# mainsheet.net
KiCad netlist of a schematic drawn in Altium Designer
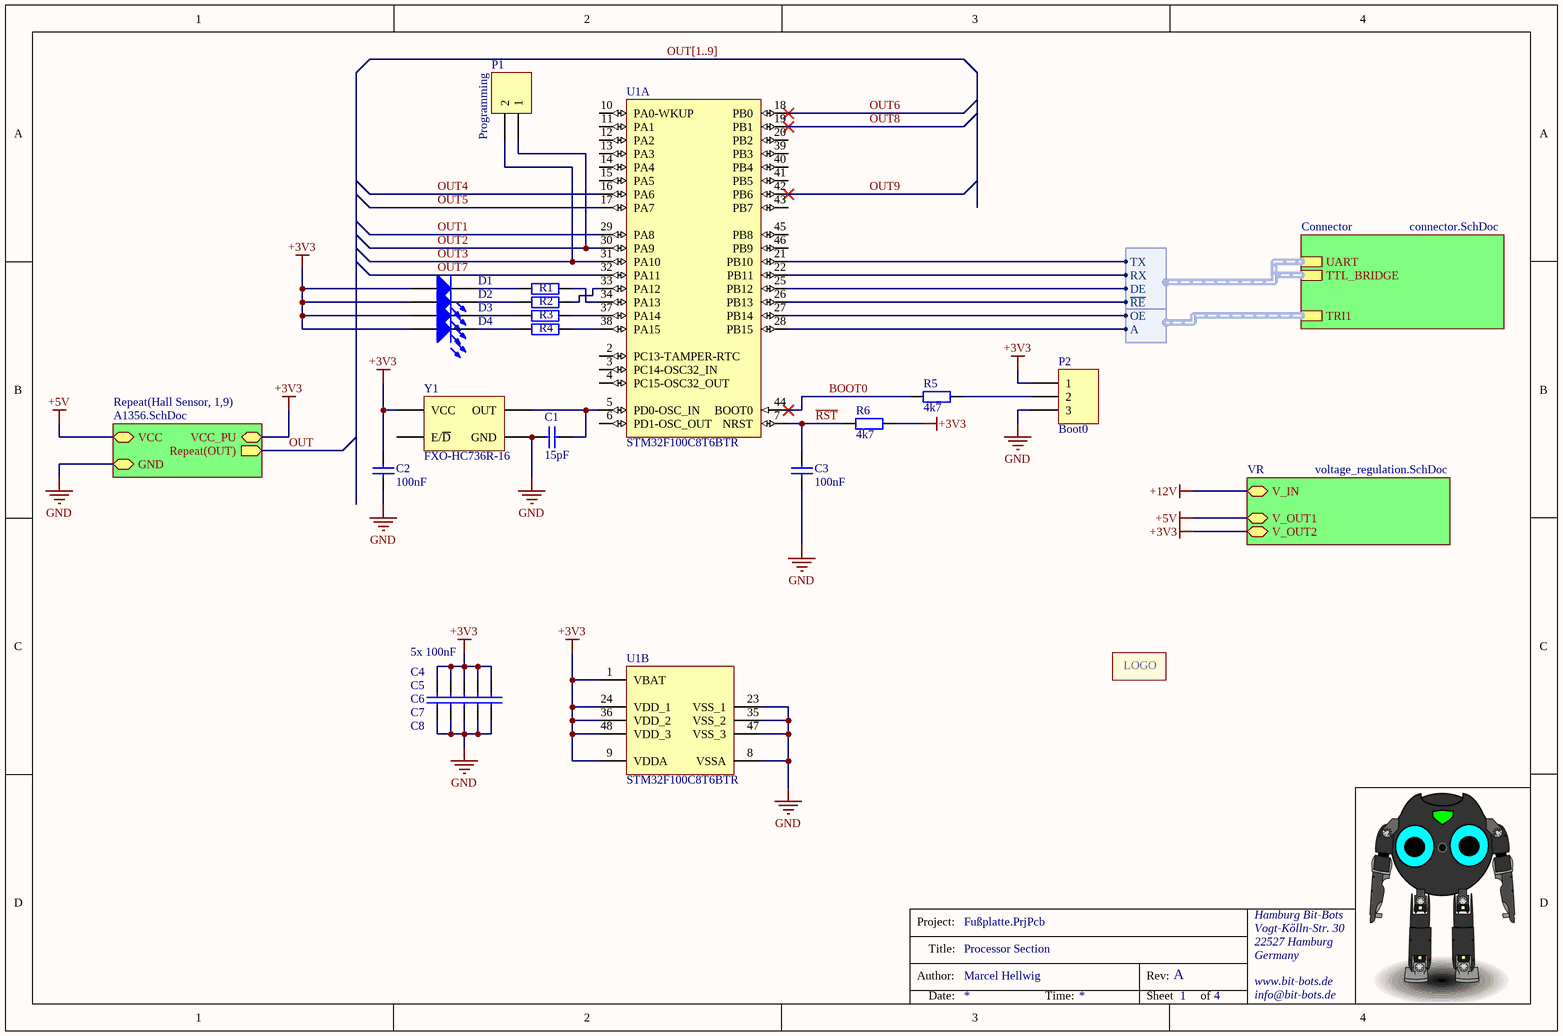
[diagram p0: mainsheet.SchDoc]

(export (version "E")
  (design (tool "Eeschema 10.0.6"))
  (components
    (comp (ref "C1")
      (value "15pF")
      (footprint "C2012")
      (description "Capacitor")
      (fields
        (field (name "MANUFACTURER") "MULTICOMP")
        (field (name "MANUFACTURER PART NUMBER") "MC0805N150J500CT")
        (field (name "PUBLISHER") "Altium Limited")
      )
      (libsource (lib "Miscellaneous Devices") (part "Cap"))
    )
    (comp (ref "C2")
      (value "100nF")
      (footprint "C2012")
      (description "Capacitor")
      (fields (field (name "PUBLISHER") "Altium Limited"))
      (libsource (lib "Miscellaneous Devices") (part "Cap"))
    )
    (comp (ref "C3")
      (value "100nF")
      (footprint "C2012")
      (description "Capacitor")
      (fields (field (name "PUBLISHER") "Altium Limited"))
      (libsource (lib "Miscellaneous Devices") (part "Cap"))
    )
    (comp (ref "C4")
      (value "100nF")
      (footprint "C2012")
      (description "Capacitor")
      (fields (field (name "PUBLISHER") "Altium Limited"))
      (libsource (lib "Miscellaneous Devices") (part "Cap"))
    )
    (comp (ref "C5")
      (value "100nF")
      (footprint "C2012")
      (description "Capacitor")
      (fields (field (name "PUBLISHER") "Altium Limited"))
      (libsource (lib "Miscellaneous Devices") (part "Cap"))
    )
    (comp (ref "C6")
      (value "100nF")
      (footprint "C2012")
      (description "Capacitor")
      (fields (field (name "PUBLISHER") "Altium Limited"))
      (libsource (lib "Miscellaneous Devices") (part "Cap"))
    )
    (comp (ref "C7")
      (value "100nF")
      (footprint "C2012")
      (description "Capacitor")
      (fields (field (name "PUBLISHER") "Altium Limited"))
      (libsource (lib "Miscellaneous Devices") (part "Cap"))
    )
    (comp (ref "C8")
      (value "100nF")
      (footprint "C2012")
      (description "Capacitor")
      (fields (field (name "PUBLISHER") "Altium Limited"))
      (libsource (lib "Miscellaneous Devices") (part "Cap"))
    )
    (comp (ref "D1")
      (value "Green")
      (footprint "MLCC2")
      (description "Typical INFRARED GaAs LED")
      (fields
        (field (name "MANUFACTURER") "VISHAY")
        (field (name "MANUFACTURER PART NUMBER") "VLMC3100-GS08")
        (field (name "PUBLISHER") "Altium Limited")
      )
      (libsource (lib "Miscellaneous Devices") (part "LED0"))
    )
    (comp (ref "D2")
      (value "Green")
      (footprint "MLCC2")
      (description "Typical INFRARED GaAs LED")
      (fields
        (field (name "MANUFACTURER") "VISHAY")
        (field (name "MANUFACTURER PART NUMBER") "VLMC3100-GS08")
        (field (name "PUBLISHER") "Altium Limited")
      )
      (libsource (lib "Miscellaneous Devices") (part "LED0"))
    )
    (comp (ref "D3")
      (value "Green")
      (footprint "MLCC2")
      (description "Typical INFRARED GaAs LED")
      (fields
        (field (name "MANUFACTURER") "VISHAY")
        (field (name "MANUFACTURER PART NUMBER") "VLMC3100-GS08")
        (field (name "PUBLISHER") "Altium Limited")
      )
      (libsource (lib "Miscellaneous Devices") (part "LED0"))
    )
    (comp (ref "D4")
      (value "Green")
      (footprint "MLCC2")
      (description "Typical INFRARED GaAs LED")
      (fields
        (field (name "MANUFACTURER") "VISHAY")
        (field (name "MANUFACTURER PART NUMBER") "VLMC3100-GS08")
        (field (name "PUBLISHER") "Altium Limited")
      )
      (libsource (lib "Miscellaneous Devices") (part "LED0"))
    )
    (comp (ref "Logo1")
      (value "Hamburg Bit-Bots Logo")
      (footprint "Logo")
      (libsource (lib "bitbots") (part "Logo"))
    )
    (comp (ref "P1")
      (value "Programming")
      (footprint "HDR1X2")
      (description "Header, 2-Pin")
      (fields (field (name "PUBLISHER") "Altium Limited"))
      (libsource (lib "Miscellaneous Connectors") (part "Header 2"))
    )
    (comp (ref "P2")
      (value "Boot0")
      (footprint "HDR1X3")
      (description "Header, 3-Pin")
      (fields (field (name "PUBLISHER") "Altium Limited"))
      (libsource (lib "Miscellaneous Connectors") (part "Header 3"))
    )
    (comp (ref "R1")
      (value "1k")
      (footprint "R2012")
      (description "Resistor")
      (fields
        (field (name "MANUFACTURER") "MULTICOMP")
        (field (name "MANUFACTURER PART NUMBER") "MC01W0805110K")
        (field (name "PUBLISHER") "Altium Limited")
      )
      (libsource (lib "Miscellaneous Devices") (part "Res2"))
    )
    (comp (ref "R2")
      (value "1k")
      (footprint "R2012")
      (description "Resistor")
      (fields
        (field (name "MANUFACTURER") "MULTICOMP")
        (field (name "MANUFACTURER PART NUMBER") "MC01W0805110K")
        (field (name "PUBLISHER") "Altium Limited")
      )
      (libsource (lib "Miscellaneous Devices") (part "Res2"))
    )
    (comp (ref "R3")
      (value "1k")
      (footprint "R2012")
      (description "Resistor")
      (fields
        (field (name "MANUFACTURER") "MULTICOMP")
        (field (name "MANUFACTURER PART NUMBER") "MC01W0805110K")
        (field (name "PUBLISHER") "Altium Limited")
      )
      (libsource (lib "Miscellaneous Devices") (part "Res2"))
    )
    (comp (ref "R4")
      (value "1k")
      (footprint "R2012")
      (description "Resistor")
      (fields
        (field (name "MANUFACTURER") "MULTICOMP")
        (field (name "MANUFACTURER PART NUMBER") "MC01W0805110K")
        (field (name "PUBLISHER") "Altium Limited")
      )
      (libsource (lib "Miscellaneous Devices") (part "Res2"))
    )
    (comp (ref "R5")
      (value "4k7")
      (footprint "R2012")
      (description "Resistor")
      (fields (field (name "PUBLISHER") "Altium Limited"))
      (libsource (lib "") (part "Res2_1"))
    )
    (comp (ref "R6")
      (value "4k7")
      (footprint "R2012")
      (description "Resistor")
      (fields (field (name "PUBLISHER") "Altium Limited"))
      (libsource (lib "") (part "Res2_1"))
    )
    (comp (ref "U1")
      (value "STM32F100C8T6BTR")
      (footprint "STM-LQFP48_L")
      (libsource (lib "Altium Content Vault") (part "MC-ARM-STM32F100X4_6_8_B-SQ48"))
    )
    (comp (ref "Y1")
      (value "FXO-HC736R-16")
      (footprint "FXO-HC73")
      (description "Oscillator with Enable Input")
      (libsource (lib "bitbots") (part "Oszillator"))
    )
  )
  (nets
    (net (code "3") (name "+3V3") (class "Default")
      (node (ref "C2") (pin "1") (pinfunction "1_1") (pintype "passive"))
      (node (ref "C4") (pin "2") (pinfunction "2_2") (pintype "passive"))
      (node (ref "C5") (pin "2") (pinfunction "2_2") (pintype "passive"))
      (node (ref "C6") (pin "2") (pinfunction "2_2") (pintype "passive"))
      (node (ref "C7") (pin "2") (pinfunction "2_2") (pintype "passive"))
      (node (ref "C8") (pin "2") (pinfunction "2_2") (pintype "passive"))
      (node (ref "D1") (pin "1") (pinfunction "A_1") (pintype "passive"))
      (node (ref "D2") (pin "1") (pinfunction "A_1") (pintype "passive"))
      (node (ref "D3") (pin "1") (pinfunction "A_1") (pintype "passive"))
      (node (ref "D4") (pin "1") (pinfunction "A_1") (pintype "passive"))
      (node (ref "P2") (pin "1") (pinfunction "1_1") (pintype "passive"))
      (node (ref "R6") (pin "2") (pinfunction "2_2") (pintype "passive"))
      (node (ref "U1") (pin "1") (pinfunction "VBAT_1") (pintype "power_in"))
      (node (ref "U1") (pin "24") (pinfunction "VDD_1_24") (pintype "power_in"))
      (node (ref "U1") (pin "36") (pinfunction "VDD_2_36") (pintype "power_in"))
      (node (ref "U1") (pin "48") (pinfunction "VDD_3_48") (pintype "power_in"))
      (node (ref "U1") (pin "9") (pinfunction "VDDA_9") (pintype "power_in"))
      (node (ref "Y1") (pin "4") (pinfunction "VCC_4") (pintype "passive"))
    )
    (net (code "6") (name "/A") (class "Default")
      (node (ref "U1") (pin "28") (pinfunction "PB15_28") (pintype "bidirectional"))
    )
    (net (code "7") (name "/BOOT0") (class "Default")
      (node (ref "R5") (pin "1") (pinfunction "1_1") (pintype "passive"))
      (node (ref "U1") (pin "44") (pinfunction "BOOT0_44") (pintype "input"))
    )
    (net (code "8") (name "/DE") (class "Default")
      (node (ref "U1") (pin "25") (pinfunction "PB12_25") (pintype "bidirectional"))
    )
    (net (code "9") (name "/OE") (class "Default")
      (node (ref "U1") (pin "27") (pinfunction "PB14_27") (pintype "bidirectional"))
    )
    (net (code "11") (name "/OUT1") (class "Default")
      (node (ref "U1") (pin "29") (pinfunction "PA8_29") (pintype "bidirectional"))
    )
    (net (code "12") (name "/OUT2") (class "Default")
      (node (ref "P1") (pin "1") (pinfunction "1_1") (pintype "passive"))
      (node (ref "U1") (pin "30") (pinfunction "PA9_30") (pintype "bidirectional"))
    )
    (net (code "13") (name "/OUT3") (class "Default")
      (node (ref "P1") (pin "2") (pinfunction "2_2") (pintype "passive"))
      (node (ref "U1") (pin "31") (pinfunction "PA10_31") (pintype "bidirectional"))
    )
    (net (code "14") (name "/OUT4") (class "Default")
      (node (ref "U1") (pin "16") (pinfunction "PA6_16") (pintype "bidirectional"))
    )
    (net (code "15") (name "/OUT5") (class "Default")
      (node (ref "U1") (pin "17") (pinfunction "PA7_17") (pintype "bidirectional"))
    )
    (net (code "16") (name "/OUT6") (class "Default")
      (node (ref "U1") (pin "18") (pinfunction "PB0_18") (pintype "bidirectional+no_connect"))
    )
    (net (code "17") (name "/OUT7") (class "Default")
      (node (ref "U1") (pin "32") (pinfunction "PA11_32") (pintype "bidirectional"))
    )
    (net (code "18") (name "/OUT8") (class "Default")
      (node (ref "U1") (pin "19") (pinfunction "PB1_19") (pintype "bidirectional+no_connect"))
    )
    (net (code "19") (name "/OUT9") (class "Default")
      (node (ref "U1") (pin "42") (pinfunction "PB6_42") (pintype "bidirectional+no_connect"))
    )
    (net (code "21") (name "/RST") (class "Default")
      (node (ref "C3") (pin "2") (pinfunction "2_2") (pintype "passive"))
      (node (ref "R6") (pin "1") (pinfunction "1_1") (pintype "passive"))
      (node (ref "U1") (pin "7") (pinfunction "NRST_7") (pintype "bidirectional"))
    )
    (net (code "22") (name "/RX") (class "Default")
      (node (ref "U1") (pin "22") (pinfunction "PB11_22") (pintype "bidirectional"))
    )
    (net (code "23") (name "/TX") (class "Default")
      (node (ref "U1") (pin "21") (pinfunction "PB10_21") (pintype "bidirectional"))
    )
    (net (code "26") (name "/~{RE}") (class "Default")
      (node (ref "U1") (pin "26") (pinfunction "PB13_26") (pintype "bidirectional"))
    )
    (net (code "27") (name "GND") (class "Default")
      (node (ref "C1") (pin "1") (pinfunction "1_1") (pintype "passive"))
      (node (ref "C2") (pin "2") (pinfunction "2_2") (pintype "passive"))
      (node (ref "C3") (pin "1") (pinfunction "1_1") (pintype "passive"))
      (node (ref "C4") (pin "1") (pinfunction "1_1") (pintype "passive"))
      (node (ref "C5") (pin "1") (pinfunction "1_1") (pintype "passive"))
      (node (ref "C6") (pin "1") (pinfunction "1_1") (pintype "passive"))
      (node (ref "C7") (pin "1") (pinfunction "1_1") (pintype "passive"))
      (node (ref "C8") (pin "1") (pinfunction "1_1") (pintype "passive"))
      (node (ref "P2") (pin "3") (pinfunction "3_3") (pintype "passive"))
      (node (ref "U1") (pin "23") (pinfunction "VSS_1_23") (pintype "power_in"))
      (node (ref "U1") (pin "35") (pinfunction "VSS_2_35") (pintype "power_in"))
      (node (ref "U1") (pin "47") (pinfunction "VSS_3_47") (pintype "power_in"))
      (node (ref "U1") (pin "8") (pinfunction "VSSA_8") (pintype "power_in"))
      (node (ref "Y1") (pin "2") (pinfunction "GND_2") (pintype "passive"))
    )
    (net (code "28") (name "Net-(D1-K)") (class "Default")
      (node (ref "D1") (pin "2") (pinfunction "K_2") (pintype "passive"))
      (node (ref "R1") (pin "2") (pinfunction "2_2") (pintype "passive"))
    )
    (net (code "29") (name "Net-(D2-K)") (class "Default")
      (node (ref "D2") (pin "2") (pinfunction "K_2") (pintype "passive"))
      (node (ref "R2") (pin "2") (pinfunction "2_2") (pintype "passive"))
    )
    (net (code "30") (name "Net-(D3-K)") (class "Default")
      (node (ref "D3") (pin "2") (pinfunction "K_2") (pintype "passive"))
      (node (ref "R3") (pin "2") (pinfunction "2_2") (pintype "passive"))
    )
    (net (code "31") (name "Net-(D4-K)") (class "Default")
      (node (ref "D4") (pin "2") (pinfunction "K_2") (pintype "passive"))
      (node (ref "R4") (pin "2") (pinfunction "2_2") (pintype "passive"))
    )
    (net (code "32") (name "Net-(P2-Pad2)") (class "Default")
      (node (ref "P2") (pin "2") (pinfunction "2_2") (pintype "passive"))
      (node (ref "R5") (pin "2") (pinfunction "2_2") (pintype "passive"))
    )
    (net (code "33") (name "Net-(U1A-PA12)") (class "Default")
      (node (ref "R2") (pin "1") (pinfunction "1_1") (pintype "passive"))
      (node (ref "U1") (pin "33") (pinfunction "PA12_33") (pintype "bidirectional"))
    )
    (net (code "34") (name "Net-(U1A-PA13)") (class "Default")
      (node (ref "R1") (pin "1") (pinfunction "1_1") (pintype "passive"))
      (node (ref "U1") (pin "34") (pinfunction "PA13_34") (pintype "bidirectional"))
    )
    (net (code "35") (name "Net-(U1A-PA14)") (class "Default")
      (node (ref "R3") (pin "1") (pinfunction "1_1") (pintype "passive"))
      (node (ref "U1") (pin "37") (pinfunction "PA14_37") (pintype "bidirectional"))
    )
    (net (code "36") (name "Net-(U1A-PA15)") (class "Default")
      (node (ref "R4") (pin "1") (pinfunction "1_1") (pintype "passive"))
      (node (ref "U1") (pin "38") (pinfunction "PA15_38") (pintype "bidirectional"))
    )
    (net (code "37") (name "Net-(U1A-PD0-OSC_IN)") (class "Default")
      (node (ref "C1") (pin "2") (pinfunction "2_2") (pintype "passive"))
      (node (ref "U1") (pin "5") (pinfunction "PD0-OSC_IN_5") (pintype "bidirectional"))
      (node (ref "Y1") (pin "3") (pinfunction "OUT_3") (pintype "passive"))
    )
    (net (code "38") (name "unconnected-(U1A-PA0-WKUP-Pad10)") (class "Default")
      (node (ref "U1") (pin "10") (pinfunction "PA0-WKUP_10") (pintype "bidirectional"))
    )
    (net (code "39") (name "unconnected-(U1A-PA1-Pad11)") (class "Default")
      (node (ref "U1") (pin "11") (pinfunction "PA1_11") (pintype "bidirectional"))
    )
    (net (code "40") (name "unconnected-(U1A-PA2-Pad12)") (class "Default")
      (node (ref "U1") (pin "12") (pinfunction "PA2_12") (pintype "bidirectional"))
    )
    (net (code "41") (name "unconnected-(U1A-PA3-Pad13)") (class "Default")
      (node (ref "U1") (pin "13") (pinfunction "PA3_13") (pintype "bidirectional"))
    )
    (net (code "42") (name "unconnected-(U1A-PA4-Pad14)") (class "Default")
      (node (ref "U1") (pin "14") (pinfunction "PA4_14") (pintype "bidirectional"))
    )
    (net (code "43") (name "unconnected-(U1A-PA5-Pad15)") (class "Default")
      (node (ref "U1") (pin "15") (pinfunction "PA5_15") (pintype "bidirectional"))
    )
    (net (code "44") (name "unconnected-(U1A-PB2-Pad20)") (class "Default")
      (node (ref "U1") (pin "20") (pinfunction "PB2_20") (pintype "bidirectional"))
    )
    (net (code "45") (name "unconnected-(U1A-PB3-Pad39)") (class "Default")
      (node (ref "U1") (pin "39") (pinfunction "PB3_39") (pintype "bidirectional"))
    )
    (net (code "46") (name "unconnected-(U1A-PB4-Pad40)") (class "Default")
      (node (ref "U1") (pin "40") (pinfunction "PB4_40") (pintype "bidirectional"))
    )
    (net (code "47") (name "unconnected-(U1A-PB5-Pad41)") (class "Default")
      (node (ref "U1") (pin "41") (pinfunction "PB5_41") (pintype "bidirectional"))
    )
    (net (code "48") (name "unconnected-(U1A-PB7-Pad43)") (class "Default")
      (node (ref "U1") (pin "43") (pinfunction "PB7_43") (pintype "bidirectional"))
    )
    (net (code "49") (name "unconnected-(U1A-PB8-Pad45)") (class "Default")
      (node (ref "U1") (pin "45") (pinfunction "PB8_45") (pintype "bidirectional"))
    )
    (net (code "50") (name "unconnected-(U1A-PB9-Pad46)") (class "Default")
      (node (ref "U1") (pin "46") (pinfunction "PB9_46") (pintype "bidirectional"))
    )
    (net (code "51") (name "unconnected-(U1A-PC13-TAMPER-RTC-Pad2)") (class "Default")
      (node (ref "U1") (pin "2") (pinfunction "PC13-TAMPER-RTC_2") (pintype "bidirectional"))
    )
    (net (code "52") (name "unconnected-(U1A-PC14-OSC32_IN-Pad3)") (class "Default")
      (node (ref "U1") (pin "3") (pinfunction "PC14-OSC32_IN_3") (pintype "bidirectional"))
    )
    (net (code "53") (name "unconnected-(U1A-PC15-OSC32_OUT-Pad4)") (class "Default")
      (node (ref "U1") (pin "4") (pinfunction "PC15-OSC32_OUT_4") (pintype "bidirectional"))
    )
    (net (code "54") (name "unconnected-(U1A-PD1-OSC_OUT-Pad6)") (class "Default")
      (node (ref "U1") (pin "6") (pinfunction "PD1-OSC_OUT_6") (pintype "bidirectional"))
    )
    (net (code "55") (name "unconnected-(Y1-E{slash}~{D}-Pad1)") (class "Default")
      (node (ref "Y1") (pin "1") (pinfunction "E/~{D}_1") (pintype "passive"))
    )
  )
)
